# temp_control.net
KiCad netlist of a schematic drawn in EAGLE
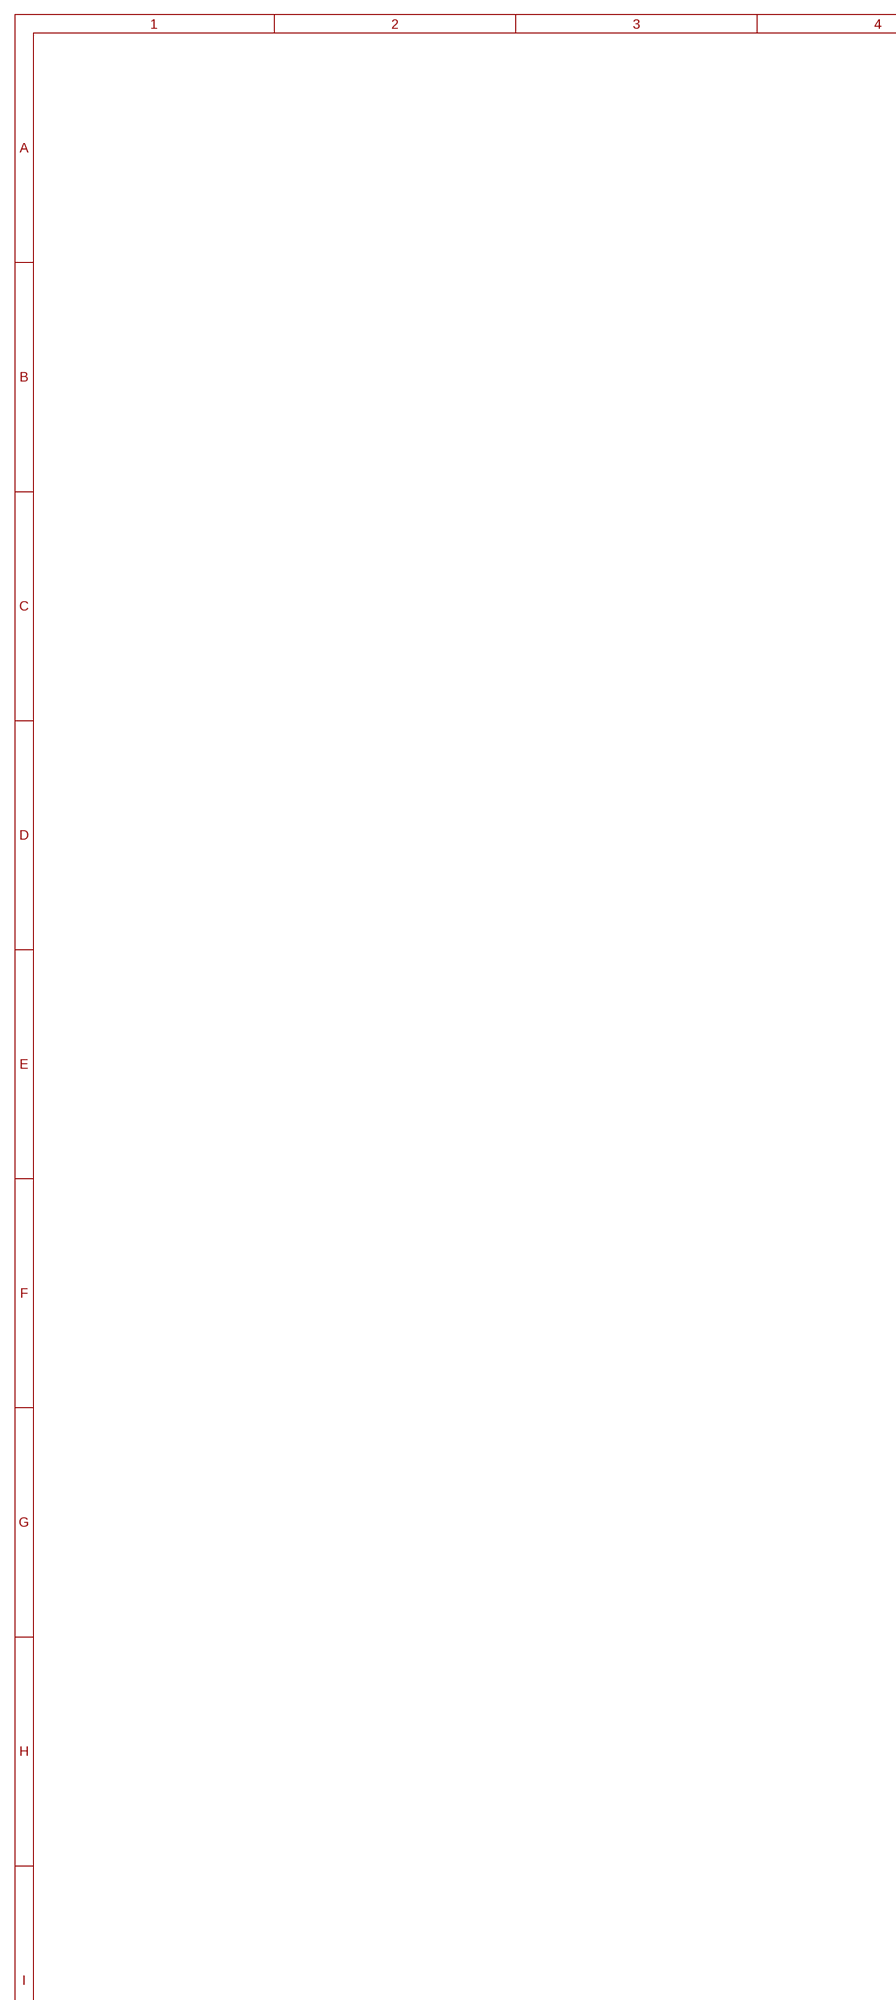
[diagram p0: schematic, sheet 1, part 1 of 2]
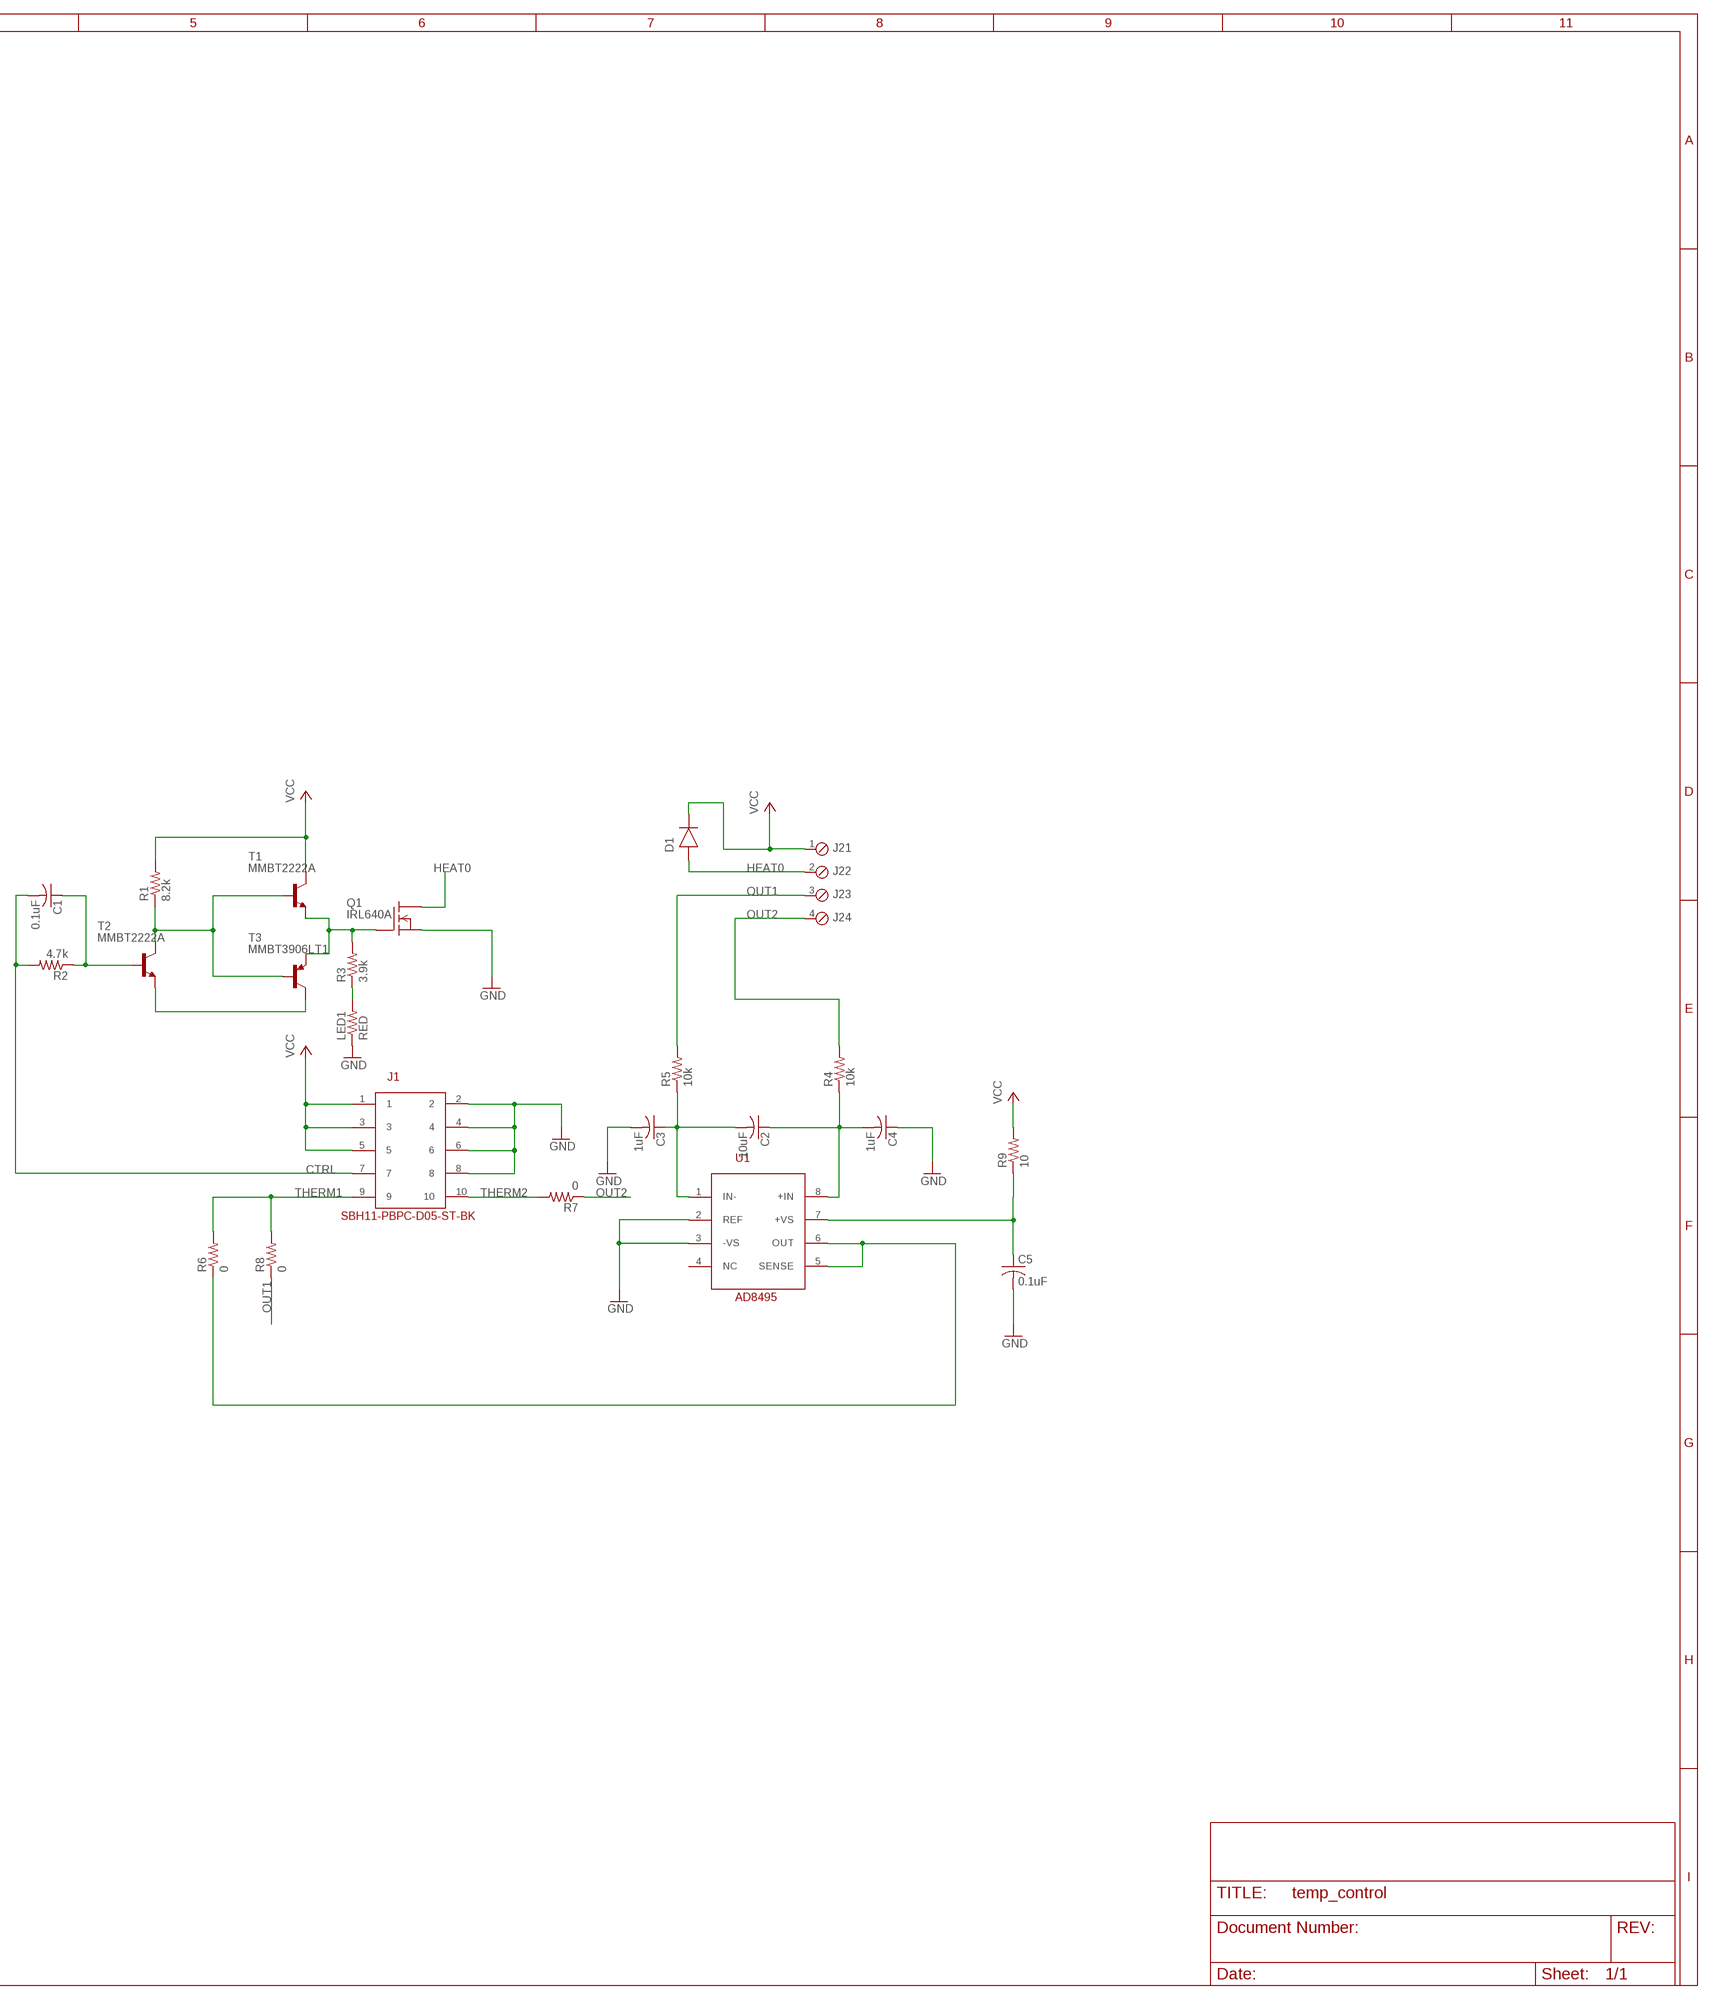
[diagram p1: schematic, sheet 1, part 2 of 2]

(export (version "E")
  (design (tool "Eeschema 10.0.6"))
  (components
    (comp (ref "C1")
      (value "0.1uF")
      (footprint "eagle-import:C0603")
      (libsource (lib "eagle-import") (part "C-USC0603"))
    )
    (comp (ref "C2")
      (value "10uF")
      (footprint "eagle-import:C0603")
      (libsource (lib "eagle-import") (part "C-USC0603"))
    )
    (comp (ref "C3")
      (value "1uF")
      (footprint "eagle-import:C0603")
      (libsource (lib "eagle-import") (part "C-USC0603"))
    )
    (comp (ref "C4")
      (value "1uF")
      (footprint "eagle-import:C0603")
      (libsource (lib "eagle-import") (part "C-USC0603"))
    )
    (comp (ref "C5")
      (value "0.1uF")
      (footprint "eagle-import:C0603")
      (libsource (lib "eagle-import") (part "C-USC0603"))
    )
    (comp (ref "D1")
      (value "B340A-13-F")
      (footprint "eagle-import:DISCRETE_SMA")
      (libsource (lib "eagle-import") (part "DISCRETE_DIODESMA"))
    )
    (comp (ref "J1")
      (value "SBH11-PBPC-D05-ST-BK")
      (footprint "eagle-import:SBH11-PBPC-D05-ST-BK")
      (libsource (lib "eagle-import") (part "SBH11-PBPC-D05-ST-BK"))
    )
    (comp (ref "J2")
      (value "OSTVN04A150")
      (footprint "eagle-import:4POL254")
      (libsource (lib "eagle-import") (part "OSTVN04A150"))
    )
    (comp (ref "LED1")
      (value "RED")
      (footprint "eagle-import:R0603")
      (libsource (lib "eagle-import") (part "R-US_R0603"))
    )
    (comp (ref "Q1")
      (value "IRL640A")
      (footprint "eagle-import:TO220")
      (libsource (lib "eagle-import") (part "SUP75N06-08"))
    )
    (comp (ref "R1")
      (value "8.2k")
      (footprint "eagle-import:R0603")
      (libsource (lib "eagle-import") (part "R-US_R0603"))
    )
    (comp (ref "R2")
      (value "4.7k")
      (footprint "eagle-import:R0603")
      (libsource (lib "eagle-import") (part "R-US_R0603"))
    )
    (comp (ref "R3")
      (value "3.9k")
      (footprint "eagle-import:R0603")
      (libsource (lib "eagle-import") (part "R-US_R0603"))
    )
    (comp (ref "R4")
      (value "10k")
      (footprint "eagle-import:R0603")
      (libsource (lib "eagle-import") (part "R-US_R0603"))
    )
    (comp (ref "R5")
      (value "10k")
      (footprint "eagle-import:R0603")
      (libsource (lib "eagle-import") (part "R-US_R0603"))
    )
    (comp (ref "R6")
      (value "0")
      (footprint "eagle-import:R0603")
      (libsource (lib "eagle-import") (part "R-US_R0603"))
    )
    (comp (ref "R7")
      (value "0")
      (footprint "eagle-import:R0603")
      (libsource (lib "eagle-import") (part "R-US_R0603"))
    )
    (comp (ref "R8")
      (value "0")
      (footprint "eagle-import:R0603")
      (libsource (lib "eagle-import") (part "R-US_R0603"))
    )
    (comp (ref "R9")
      (value "10")
      (footprint "eagle-import:R0603")
      (libsource (lib "eagle-import") (part "R-US_R0603"))
    )
    (comp (ref "T1")
      (value "MMBT2222A")
      (footprint "eagle-import:SOT23-BEC")
      (libsource (lib "eagle-import") (part "-NPN-SOT23-BECMMBT2222ALT1"))
    )
    (comp (ref "T2")
      (value "MMBT2222A")
      (footprint "eagle-import:SOT23-BEC")
      (libsource (lib "eagle-import") (part "-NPN-SOT23-BECMMBT2222ALT1"))
    )
    (comp (ref "T3")
      (value "MMBT3906LT1")
      (footprint "eagle-import:SOT23-BEC")
      (libsource (lib "eagle-import") (part "-PNP-SOT23-BECMMBT3906LT1"))
    )
    (comp (ref "U1")
      (value "AD8495")
      (footprint "eagle-import:MSOP08")
      (libsource (lib "eagle-import") (part "AD8495"))
    )
  )
  (nets
    (net (code "1") (name "/CTRL") (class "Default")
      (node (ref "C1") (pin "2") (pinfunction "2_2") (pintype "passive"))
      (node (ref "J1") (pin "7") (pinfunction "7_7") (pintype "bidirectional"))
      (node (ref "R2") (pin "2") (pinfunction "2_2") (pintype "passive"))
    )
    (net (code "2") (name "/HEAT0") (class "Default")
      (node (ref "D1") (pin "A") (pinfunction "A_A") (pintype "bidirectional"))
      (node (ref "J2") (pin "2") (pinfunction "1_2") (pintype "passive"))
      (node (ref "Q1") (pin "2") (pinfunction "D_2") (pintype "passive"))
    )
    (net (code "3") (name "/OUT1") (class "Default")
      (node (ref "J2") (pin "3") (pinfunction "1_3") (pintype "passive"))
      (node (ref "R5") (pin "2") (pinfunction "2_2") (pintype "passive"))
      (node (ref "R8") (pin "1") (pinfunction "1_1") (pintype "passive"))
    )
    (net (code "4") (name "/OUT2") (class "Default")
      (node (ref "J2") (pin "4") (pinfunction "1_4") (pintype "passive"))
      (node (ref "R4") (pin "2") (pinfunction "2_2") (pintype "passive"))
      (node (ref "R7") (pin "1") (pinfunction "1_1") (pintype "passive"))
    )
    (net (code "5") (name "/THERM1") (class "Default")
      (node (ref "J1") (pin "9") (pinfunction "9_9") (pintype "bidirectional"))
      (node (ref "R6") (pin "2") (pinfunction "2_2") (pintype "passive"))
      (node (ref "R8") (pin "2") (pinfunction "2_2") (pintype "passive"))
    )
    (net (code "6") (name "/THERM2") (class "Default")
      (node (ref "J1") (pin "10") (pinfunction "10_10") (pintype "bidirectional"))
      (node (ref "R7") (pin "2") (pinfunction "2_2") (pintype "passive"))
    )
    (net (code "7") (name "GND") (class "Default")
      (node (ref "C3") (pin "2") (pinfunction "2_2") (pintype "passive"))
      (node (ref "C4") (pin "1") (pinfunction "1_1") (pintype "passive"))
      (node (ref "C5") (pin "2") (pinfunction "2_2") (pintype "passive"))
      (node (ref "J1") (pin "2") (pinfunction "2_2") (pintype "bidirectional"))
      (node (ref "J1") (pin "4") (pinfunction "4_4") (pintype "bidirectional"))
      (node (ref "J1") (pin "6") (pinfunction "6_6") (pintype "bidirectional"))
      (node (ref "J1") (pin "8") (pinfunction "8_8") (pintype "bidirectional"))
      (node (ref "LED1") (pin "1") (pinfunction "1_1") (pintype "passive"))
      (node (ref "Q1") (pin "3") (pinfunction "S_3") (pintype "passive"))
      (node (ref "U1") (pin "2") (pinfunction "REF_2") (pintype "bidirectional"))
      (node (ref "U1") (pin "3") (pinfunction "-VS_3") (pintype "bidirectional"))
    )
    (net (code "8") (name "Net-(C1-Pad1)") (class "Default")
      (node (ref "C1") (pin "1") (pinfunction "1_1") (pintype "passive"))
      (node (ref "R2") (pin "1") (pinfunction "1_1") (pintype "passive"))
      (node (ref "T2") (pin "B") (pinfunction "B_B") (pintype "passive"))
    )
    (net (code "9") (name "Net-(LED1-Pad2)") (class "Default")
      (node (ref "LED1") (pin "2") (pinfunction "2_2") (pintype "passive"))
      (node (ref "R3") (pin "1") (pinfunction "1_1") (pintype "passive"))
    )
    (net (code "10") (name "Net-(Q1-G)") (class "Default")
      (node (ref "Q1") (pin "1") (pinfunction "G_1") (pintype "passive"))
      (node (ref "R3") (pin "2") (pinfunction "2_2") (pintype "passive"))
      (node (ref "T1") (pin "E") (pinfunction "E_E") (pintype "passive"))
      (node (ref "T3") (pin "E") (pinfunction "E_E") (pintype "passive"))
    )
    (net (code "11") (name "Net-(R1-Pad1)") (class "Default")
      (node (ref "R1") (pin "1") (pinfunction "1_1") (pintype "passive"))
      (node (ref "T1") (pin "B") (pinfunction "B_B") (pintype "passive"))
      (node (ref "T2") (pin "C") (pinfunction "C_C") (pintype "passive"))
      (node (ref "T3") (pin "B") (pinfunction "B_B") (pintype "passive"))
    )
    (net (code "12") (name "Net-(T2-PadE)") (class "Default")
      (node (ref "T2") (pin "E") (pinfunction "E_E") (pintype "passive"))
      (node (ref "T3") (pin "C") (pinfunction "C_C") (pintype "passive"))
    )
    (net (code "13") (name "Net-(U1-+IN)") (class "Default")
      (node (ref "C2") (pin "1") (pinfunction "1_1") (pintype "passive"))
      (node (ref "C4") (pin "2") (pinfunction "2_2") (pintype "passive"))
      (node (ref "R4") (pin "1") (pinfunction "1_1") (pintype "passive"))
      (node (ref "U1") (pin "8") (pinfunction "+IN_8") (pintype "bidirectional"))
    )
    (net (code "14") (name "Net-(U1-+VS)") (class "Default")
      (node (ref "C5") (pin "1") (pinfunction "1_1") (pintype "passive"))
      (node (ref "R9") (pin "1") (pinfunction "1_1") (pintype "passive"))
      (node (ref "U1") (pin "7") (pinfunction "+VS_7") (pintype "bidirectional"))
    )
    (net (code "15") (name "Net-(U1-IN-)") (class "Default")
      (node (ref "C2") (pin "2") (pinfunction "2_2") (pintype "passive"))
      (node (ref "C3") (pin "1") (pinfunction "1_1") (pintype "passive"))
      (node (ref "R5") (pin "1") (pinfunction "1_1") (pintype "passive"))
      (node (ref "U1") (pin "1") (pinfunction "IN-_1") (pintype "bidirectional"))
    )
    (net (code "16") (name "Net-(U1-OUT)") (class "Default")
      (node (ref "R6") (pin "1") (pinfunction "1_1") (pintype "passive"))
      (node (ref "U1") (pin "5") (pinfunction "SENSE_5") (pintype "bidirectional"))
      (node (ref "U1") (pin "6") (pinfunction "OUT_6") (pintype "bidirectional"))
    )
    (net (code "17") (name "VCC") (class "Default")
      (node (ref "D1") (pin "C") (pinfunction "C_C") (pintype "bidirectional"))
      (node (ref "J1") (pin "1") (pinfunction "1_1") (pintype "bidirectional"))
      (node (ref "J1") (pin "3") (pinfunction "3_3") (pintype "bidirectional"))
      (node (ref "J1") (pin "5") (pinfunction "5_5") (pintype "bidirectional"))
      (node (ref "J2") (pin "1") (pinfunction "1_1") (pintype "passive"))
      (node (ref "R1") (pin "2") (pinfunction "2_2") (pintype "passive"))
      (node (ref "R9") (pin "2") (pinfunction "2_2") (pintype "passive"))
      (node (ref "T1") (pin "C") (pinfunction "C_C") (pintype "passive"))
    )
    (net (code "18") (name "unconnected-(U1-NC-Pad4)") (class "Default")
      (node (ref "U1") (pin "4") (pinfunction "NC_4") (pintype "bidirectional"))
    )
  )
)
